# imp-watt-meter.net
KiCad netlist of a schematic drawn in EAGLE
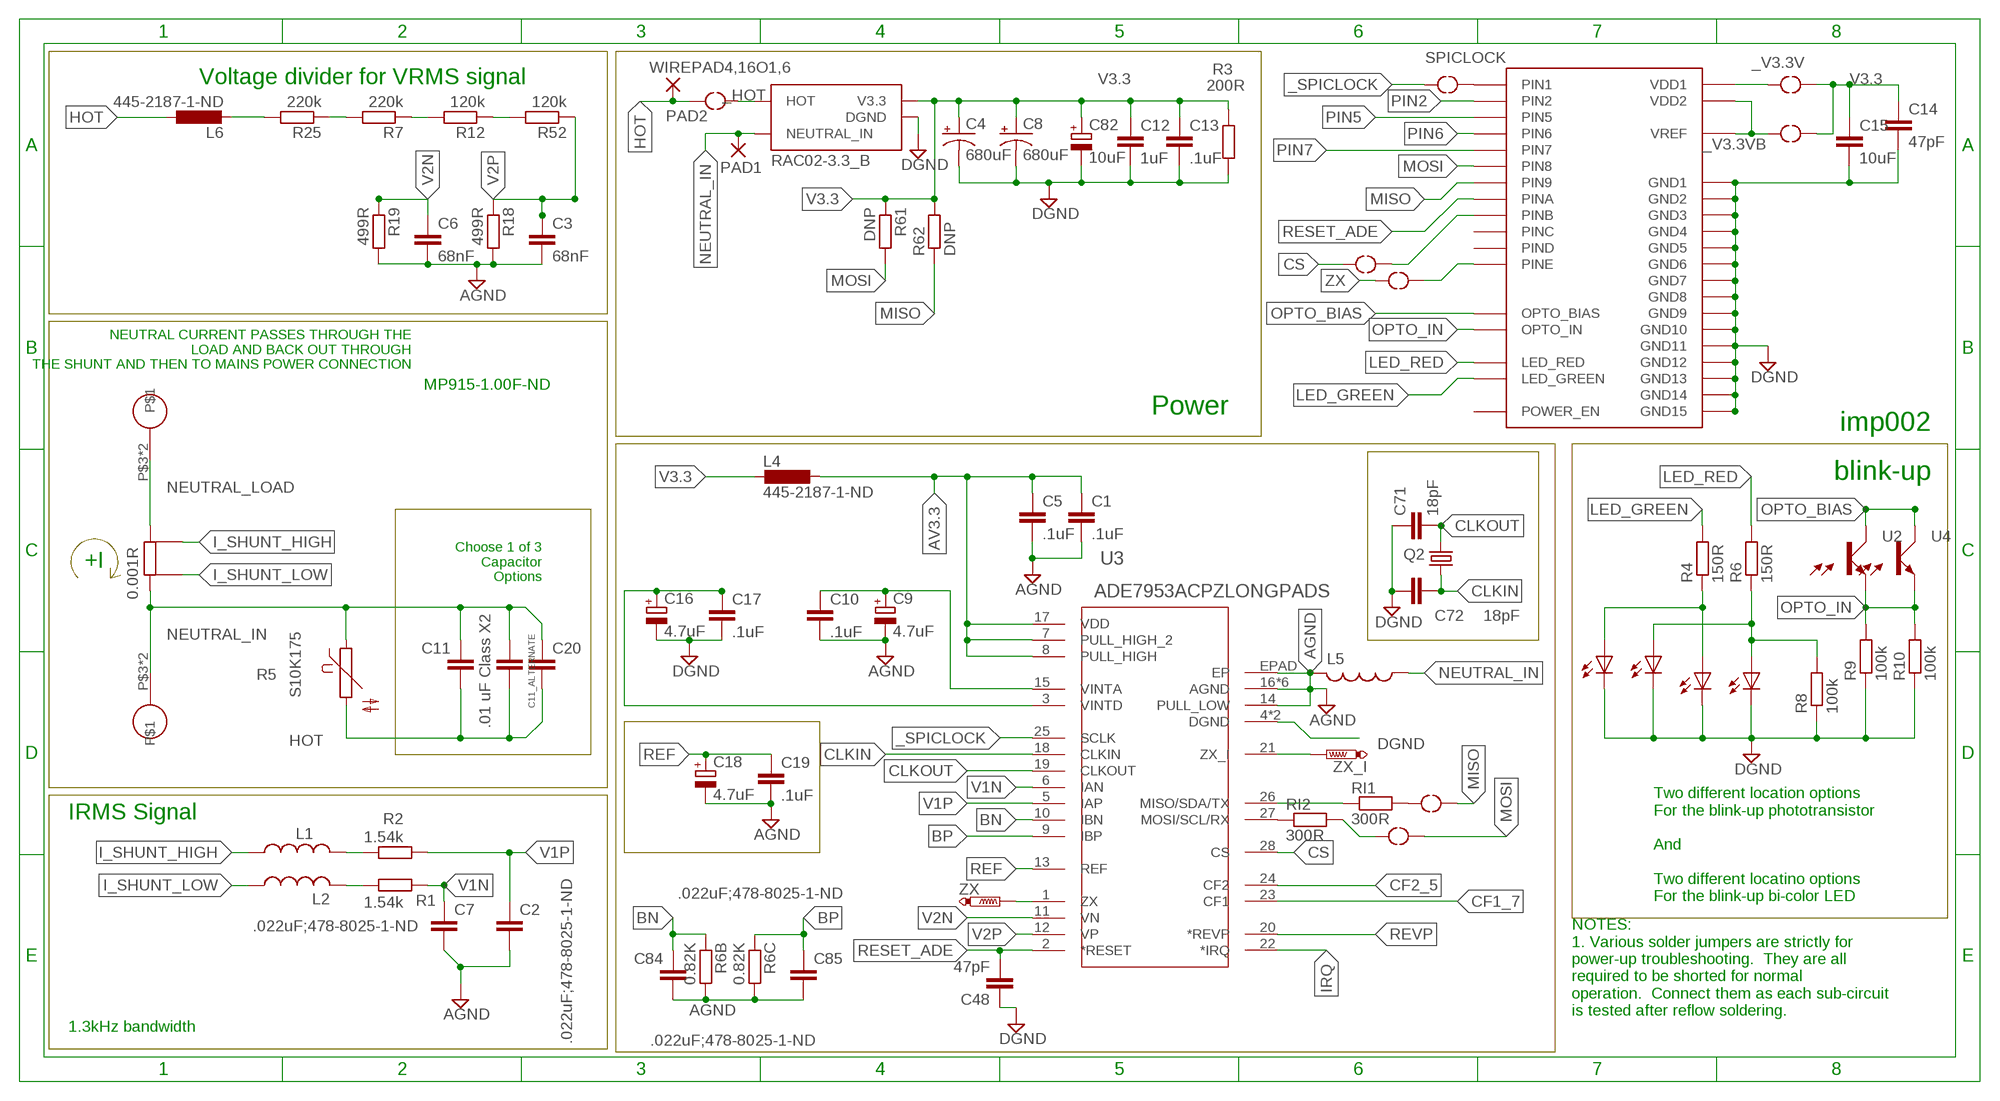
[diagram p0: schematic, sheet 1]

(export (version "E")
  (design (tool "Eeschema 10.0.6"))
  (components
    (comp (ref "0.001R")
      (value "WSLP2726L5000FEA")
      (footprint "eagle-import:WSLP276_VISHAY")
      (libsource (lib "eagle-import") (part "WSLP2726L5000FEA"))
    )
    (comp (ref "C1")
      (value ".1uF")
      (footprint "eagle-import:C0805K@1")
      (libsource (lib "eagle-import") (part "resistor_C-EUC0805K"))
    )
    (comp (ref "C2")
      (value ".022uF;478-8025-1-ND")
      (footprint "eagle-import:C0805K@1")
      (libsource (lib "eagle-import") (part "resistor_C-EUC0805K"))
    )
    (comp (ref "C3")
      (value "68nF")
      (footprint "eagle-import:C0805K@1")
      (libsource (lib "eagle-import") (part "resistor_C-EUC0805K"))
    )
    (comp (ref "C4")
      (value "680uF")
      (footprint "eagle-import:PANASONIC_D")
      (libsource (lib "eagle-import") (part "CAP_POLD"))
    )
    (comp (ref "C5")
      (value ".1uF")
      (footprint "eagle-import:C0805K@1")
      (libsource (lib "eagle-import") (part "resistor_C-EUC0805K"))
    )
    (comp (ref "C6")
      (value "68nF")
      (footprint "eagle-import:C0805K@1")
      (libsource (lib "eagle-import") (part "resistor_C-EUC0805K"))
    )
    (comp (ref "C7")
      (value ".022uF;478-8025-1-ND")
      (footprint "eagle-import:C0805K@1")
      (libsource (lib "eagle-import") (part "resistor_C-EUC0805K"))
    )
    (comp (ref "C8")
      (value "680uF")
      (footprint "eagle-import:PANASONIC_D")
      (libsource (lib "eagle-import") (part "CAP_POLD"))
    )
    (comp (ref "C9")
      (value "4.7uF")
      (footprint "eagle-import:A_3216-18R")
      (libsource (lib "eagle-import") (part "CPOL-EUA/3216-18R"))
    )
    (comp (ref "C10")
      (value ".1uF")
      (footprint "eagle-import:C0805K@1")
      (libsource (lib "eagle-import") (part "resistor_C-EUC0805K"))
    )
    (comp (ref "C11")
      (value ".01 uF Class X2")
      (footprint "eagle-import:C2220K")
      (libsource (lib "eagle-import") (part "C-EUC2220K"))
    )
    (comp (ref "C11_ALTERNATE")
      (value ".01 uF Class X2")
      (footprint "eagle-import:C2220K")
      (libsource (lib "eagle-import") (part "C-EUC2220K"))
    )
    (comp (ref "C12")
      (value "1uF")
      (footprint "eagle-import:C1206K")
      (libsource (lib "eagle-import") (part "resistor_C-EUC1206K"))
    )
    (comp (ref "C13")
      (value ".1uF")
      (footprint "eagle-import:C0805K@1")
      (libsource (lib "eagle-import") (part "resistor_C-EUC0805K"))
    )
    (comp (ref "C14")
      (value "47pF")
      (footprint "eagle-import:C0805K@1")
      (libsource (lib "eagle-import") (part "resistor_C-EUC0805K"))
    )
    (comp (ref "C15")
      (value "10uF")
      (footprint "eagle-import:1206")
      (libsource (lib "eagle-import") (part "CAP1206"))
    )
    (comp (ref "C16")
      (value "4.7uF")
      (footprint "eagle-import:A_3216-18R")
      (libsource (lib "eagle-import") (part "CPOL-EUA/3216-18R"))
    )
    (comp (ref "C17")
      (value ".1uF")
      (footprint "eagle-import:C0805K@1")
      (libsource (lib "eagle-import") (part "resistor_C-EUC0805K"))
    )
    (comp (ref "C18")
      (value "4.7uF")
      (footprint "eagle-import:A_3216-18R")
      (libsource (lib "eagle-import") (part "CPOL-EUA/3216-18R"))
    )
    (comp (ref "C19")
      (value ".1uF")
      (footprint "eagle-import:C0805K@1")
      (libsource (lib "eagle-import") (part "resistor_C-EUC0805K"))
    )
    (comp (ref "C20")
      (value "C10/4")
      (footprint "eagle-import:C10B4")
      (libsource (lib "eagle-import") (part "C10/4"))
    )
    (comp (ref "C48")
      (value "47pF")
      (footprint "eagle-import:C0805K@1")
      (libsource (lib "eagle-import") (part "resistor_C-EUC0805K"))
    )
    (comp (ref "C71")
      (value "18pF")
      (footprint "eagle-import:C0805K@1")
      (libsource (lib "eagle-import") (part "resistor_C-EUC0805K"))
    )
    (comp (ref "C72")
      (value "18pF")
      (footprint "eagle-import:C0805K@1")
      (libsource (lib "eagle-import") (part "resistor_C-EUC0805K"))
    )
    (comp (ref "C82")
      (value "10uF")
      (footprint "eagle-import:A_3216-18R")
      (libsource (lib "eagle-import") (part "CPOL-EUA/3216-18R"))
    )
    (comp (ref "C84")
      (value ".022uF;478-8025-1-ND")
      (footprint "eagle-import:C0805K@1")
      (libsource (lib "eagle-import") (part "resistor_C-EUC0805K"))
    )
    (comp (ref "C85")
      (value ".022uF;478-8025-1-ND")
      (footprint "eagle-import:C0805K@1")
      (libsource (lib "eagle-import") (part "resistor_C-EUC0805K"))
    )
    (comp (ref "L1")
      (value "L-USL4516C")
      (footprint "eagle-import:L4516C")
      (libsource (lib "eagle-import") (part "L-USL4516C"))
    )
    (comp (ref "L2")
      (value "L-USL4516C")
      (footprint "eagle-import:L4516C")
      (libsource (lib "eagle-import") (part "L-USL4516C"))
    )
    (comp (ref "L4")
      (value "445-2187-1-ND")
      (footprint "eagle-import:L2012C")
      (libsource (lib "eagle-import") (part "L-EUL2012C"))
    )
    (comp (ref "L5")
      (value "L-USL4516C")
      (footprint "eagle-import:L4516C")
      (libsource (lib "eagle-import") (part "L-USL4516C"))
    )
    (comp (ref "L6")
      (value "445-2187-1-ND")
      (footprint "eagle-import:L2012C")
      (libsource (lib "eagle-import") (part "L-EUL2012C"))
    )
    (comp (ref "PAD1")
      (value "WIREPAD4,16O1,6")
      (footprint "eagle-import:4,16O1,6")
      (libsource (lib "eagle-import") (part "WIREPAD4,16O1,6"))
    )
    (comp (ref "PAD2")
      (value "WIREPAD4,16O1,6")
      (footprint "eagle-import:4,16O1,6")
      (libsource (lib "eagle-import") (part "WIREPAD4,16O1,6"))
    )
    (comp (ref "Q2")
      (value "535-10200-1-ND")
      (footprint "eagle-import:SM49")
      (libsource (lib "eagle-import") (part "CRYSTALSM49"))
    )
    (comp (ref "R1")
      (value "1.54k")
      (footprint "eagle-import:C0805K")
      (libsource (lib "eagle-import") (part "R-EU_"))
    )
    (comp (ref "R2")
      (value "1.54k")
      (footprint "eagle-import:C0805K")
      (libsource (lib "eagle-import") (part "R-EU_"))
    )
    (comp (ref "R3")
      (value "200R")
      (footprint "eagle-import:M1206")
      (libsource (lib "eagle-import") (part "R-EU_M1206"))
    )
    (comp (ref "R4")
      (value "150R")
      (footprint "eagle-import:R0805")
      (libsource (lib "eagle-import") (part "R-EU_R0805"))
    )
    (comp (ref "R5")
      (value "S10K175")
      (footprint "eagle-import:S10K175")
      (libsource (lib "eagle-import") (part "S10K175"))
    )
    (comp (ref "R6")
      (value "150R")
      (footprint "eagle-import:R0805")
      (libsource (lib "eagle-import") (part "R-EU_R0805"))
    )
    (comp (ref "R6B")
      (value "0.82K")
      (footprint "eagle-import:C0805K")
      (libsource (lib "eagle-import") (part "R-EU_"))
    )
    (comp (ref "R6C")
      (value "0.82K")
      (footprint "eagle-import:C0805K")
      (libsource (lib "eagle-import") (part "R-EU_"))
    )
    (comp (ref "R7")
      (value "220k")
      (footprint "eagle-import:R2010")
      (libsource (lib "eagle-import") (part "R-EU_R2010"))
    )
    (comp (ref "R8")
      (value "100k")
      (footprint "eagle-import:R0805")
      (libsource (lib "eagle-import") (part "R-EU_R0805"))
    )
    (comp (ref "R9")
      (value "100k")
      (footprint "eagle-import:R0805")
      (libsource (lib "eagle-import") (part "R-EU_R0805"))
    )
    (comp (ref "R10")
      (value "100k")
      (footprint "eagle-import:R0805")
      (libsource (lib "eagle-import") (part "R-EU_R0805"))
    )
    (comp (ref "R12")
      (value "120k")
      (footprint "eagle-import:M1206")
      (libsource (lib "eagle-import") (part "R-EU_M1206"))
    )
    (comp (ref "R18")
      (value "499R")
      (footprint "eagle-import:C0805K")
      (libsource (lib "eagle-import") (part "R-EU_"))
    )
    (comp (ref "R19")
      (value "499R")
      (footprint "eagle-import:C0805K")
      (libsource (lib "eagle-import") (part "R-EU_"))
    )
    (comp (ref "R25")
      (value "220k")
      (footprint "eagle-import:R2010")
      (libsource (lib "eagle-import") (part "R-EU_R2010"))
    )
    (comp (ref "R52")
      (value "120k")
      (footprint "eagle-import:M1206")
      (libsource (lib "eagle-import") (part "R-EU_M1206"))
    )
    (comp (ref "R61")
      (value "DNP")
      (footprint "eagle-import:C0805K")
      (libsource (lib "eagle-import") (part "R-EU_"))
    )
    (comp (ref "R62")
      (value "DNP")
      (footprint "eagle-import:C0805K")
      (libsource (lib "eagle-import") (part "R-EU_"))
    )
    (comp (ref "RI1")
      (value "300R")
      (footprint "eagle-import:R0805@1")
      (libsource (lib "eagle-import") (part "R-US_R0805"))
    )
    (comp (ref "RI2")
      (value "300R")
      (footprint "eagle-import:R0805@1")
      (libsource (lib "eagle-import") (part "R-US_R0805"))
    )
    (comp (ref "U$1")
      (value "RAC02-3.3_B")
      (footprint "eagle-import:RAC02_B")
      (libsource (lib "eagle-import") (part "RAC02-3.3_B"))
    )
    (comp (ref "U$2")
      (value "KEYSTONE_FASTON")
      (footprint "eagle-import:KEYSTONE_FASTON_0.25")
      (libsource (lib "eagle-import") (part "KEYSTONE_FASTON"))
    )
    (comp (ref "U$5")
      (value "IMP002MANUFACTURING")
      (footprint "eagle-import:IMP002")
      (libsource (lib "eagle-import") (part "IMP002MANUFACTURING"))
    )
    (comp (ref "U$10")
      (value "JUMPER2B")
      (footprint "eagle-import:SOLDER_JUMPER2B")
      (libsource (lib "eagle-import") (part "JUMPER2B"))
    )
    (comp (ref "U$11")
      (value "JUMPER2B")
      (footprint "eagle-import:SOLDER_JUMPER2B")
      (libsource (lib "eagle-import") (part "JUMPER2B"))
    )
    (comp (ref "U$12")
      (value "JUMPER2B")
      (footprint "eagle-import:SOLDER_JUMPER2B")
      (libsource (lib "eagle-import") (part "JUMPER2B"))
    )
    (comp (ref "U$13")
      (value "JUMPER2B")
      (footprint "eagle-import:SOLDER_JUMPER2B")
      (libsource (lib "eagle-import") (part "JUMPER2B"))
    )
    (comp (ref "U$15")
      (value "JUMPER2B")
      (footprint "eagle-import:SOLDER_JUMPER2B")
      (libsource (lib "eagle-import") (part "JUMPER2B"))
    )
    (comp (ref "U$16")
      (value "JUMPER3")
      (footprint "eagle-import:SOLDER_JUMPER3")
      (libsource (lib "eagle-import") (part "JUMPER3"))
    )
    (comp (ref "U$17")
      (value "KEYSTONE_FASTON")
      (footprint "eagle-import:KEYSTONE_FASTON_0.25")
      (libsource (lib "eagle-import") (part "KEYSTONE_FASTON"))
    )
    (comp (ref "U$18")
      (value "JUMPER3")
      (footprint "eagle-import:SOLDER_JUMPER3")
      (libsource (lib "eagle-import") (part "JUMPER3"))
    )
    (comp (ref "U$19")
      (value "JUMPER2B")
      (footprint "eagle-import:SOLDER_JUMPER2B")
      (libsource (lib "eagle-import") (part "JUMPER2B"))
    )
    (comp (ref "U1")
      (value "LED_DUAL")
      (footprint "eagle-import:LED-BICOLOR")
      (libsource (lib "eagle-import") (part "LED_DUAL"))
    )
    (comp (ref "U2")
      (value "PHOTOTRANSISTOR0603")
      (footprint "eagle-import:0603")
      (libsource (lib "eagle-import") (part "PHOTOTRANSISTOR0603"))
    )
    (comp (ref "U3")
      (value "ADE7953ACPZLONGPADS")
      (footprint "eagle-import:VQFN-28-D")
      (libsource (lib "eagle-import") (part "ADE7953ACPZ5.0"))
    )
    (comp (ref "U4")
      (value "PHOTOTRANSISTOR0603")
      (footprint "eagle-import:0603")
      (libsource (lib "eagle-import") (part "PHOTOTRANSISTOR0603"))
    )
    (comp (ref "U5")
      (value "LED_DUAL")
      (footprint "eagle-import:LED-BICOLOR")
      (libsource (lib "eagle-import") (part "LED_DUAL"))
    )
    (comp (ref "ZX")
      (value "PTR1TP08R")
      (footprint "eagle-import:TP08R")
      (libsource (lib "eagle-import") (part "PTR1TP08R"))
    )
    (comp (ref "ZX_I")
      (value "PTR1TP08R")
      (footprint "eagle-import:TP08R")
      (libsource (lib "eagle-import") (part "PTR1TP08R"))
    )
  )
  (nets
    (net (code "1") (name "/NEUTRAL_LOAD") (class "Default")
      (node (ref "0.001R") (pin "P$1") (pinfunction "1_P$1") (pintype "passive"))
      (node (ref "0.001R") (pin "P$5") (pinfunction "1_P$5") (pintype "passive"))
      (node (ref "0.001R") (pin "P$6") (pinfunction "1_P$6") (pintype "passive"))
      (node (ref "0.001R") (pin "P$7") (pinfunction "1_P$7") (pintype "passive"))
      (node (ref "U$2") (pin "P$3") (pinfunction "P$1_P$3") (pintype "bidirectional"))
      (node (ref "U$2") (pin "P$4") (pinfunction "P$1_P$4") (pintype "bidirectional"))
    )
    (net (code "3") (name "/_HOT") (class "Default")
      (node (ref "U$1") (pin "P$2") (pinfunction "HOT_P$2") (pintype "input"))
      (node (ref "U$1") (pin "P$7") (pinfunction "HOT_P$7") (pintype "input"))
      (node (ref "U$19") (pin "P$2") (pinfunction "P$2_P$2") (pintype "bidirectional"))
    )
    (net (code "4") (name "/_V3.3V") (class "Default")
      (node (ref "U$16") (pin "P$2") (pinfunction "P$2_P$2") (pintype "bidirectional"))
      (node (ref "U$5") (pin "PAD18") (pinfunction "VDD1_PAD18") (pintype "bidirectional"))
    )
    (net (code "5") (name "/_V3.3VB") (class "Default")
      (node (ref "U$18") (pin "P$2") (pinfunction "P$2_P$2") (pintype "bidirectional"))
      (node (ref "U$5") (pin "PAD33") (pinfunction "VDD2_PAD33") (pintype "bidirectional"))
      (node (ref "U$5") (pin "PAD34") (pinfunction "VREF_PAD34") (pintype "bidirectional"))
    )
    (net (code "6") (name "AGND") (class "Default")
      (node (ref "C1") (pin "2") (pinfunction "2_2") (pintype "passive"))
      (node (ref "C10") (pin "2") (pinfunction "2_2") (pintype "passive"))
      (node (ref "C18") (pin "-") (pinfunction "-_-") (pintype "passive"))
      (node (ref "C19") (pin "2") (pinfunction "2_2") (pintype "passive"))
      (node (ref "C2") (pin "2") (pinfunction "2_2") (pintype "passive"))
      (node (ref "C3") (pin "2") (pinfunction "2_2") (pintype "passive"))
      (node (ref "C5") (pin "2") (pinfunction "2_2") (pintype "passive"))
      (node (ref "C6") (pin "2") (pinfunction "2_2") (pintype "passive"))
      (node (ref "C7") (pin "2") (pinfunction "2_2") (pintype "passive"))
      (node (ref "C84") (pin "2") (pinfunction "2_2") (pintype "passive"))
      (node (ref "C85") (pin "2") (pinfunction "2_2") (pintype "passive"))
      (node (ref "C9") (pin "-") (pinfunction "-_-") (pintype "passive"))
      (node (ref "L5") (pin "2") (pinfunction "2_2") (pintype "passive"))
      (node (ref "R18") (pin "2") (pinfunction "2_2") (pintype "passive"))
      (node (ref "R19") (pin "2") (pinfunction "2_2") (pintype "passive"))
      (node (ref "R6B") (pin "2") (pinfunction "2_2") (pintype "passive"))
      (node (ref "R6C") (pin "2") (pinfunction "2_2") (pintype "passive"))
      (node (ref "U3") (pin "14") (pinfunction "PULL_LOW_14") (pintype "passive"))
      (node (ref "U3") (pin "16") (pinfunction "AGND_16") (pintype "passive"))
      (node (ref "U3") (pin "29") (pinfunction "AGND_29") (pintype "passive"))
      (node (ref "U3") (pin "30") (pinfunction "AGND_30") (pintype "passive"))
      (node (ref "U3") (pin "31") (pinfunction "AGND_31") (pintype "passive"))
      (node (ref "U3") (pin "32") (pinfunction "AGND_32") (pintype "passive"))
      (node (ref "U3") (pin "EPAD") (pinfunction "EP_EPAD") (pintype "passive"))
      (node (ref "U3") (pin "_AGND") (pinfunction "AGND__AGND") (pintype "passive"))
    )
    (net (code "7") (name "AV3.3") (class "Default")
      (node (ref "C1") (pin "1") (pinfunction "1_1") (pintype "passive"))
      (node (ref "C5") (pin "1") (pinfunction "1_1") (pintype "passive"))
      (node (ref "L4") (pin "1") (pinfunction "1_1") (pintype "passive"))
      (node (ref "U3") (pin "17") (pinfunction "VDD_17") (pintype "passive"))
      (node (ref "U3") (pin "7") (pinfunction "PULL_HIGH_2_7") (pintype "passive"))
      (node (ref "U3") (pin "8") (pinfunction "PULL_HIGH_8") (pintype "passive"))
    )
    (net (code "8") (name "BN") (class "Default")
      (node (ref "C84") (pin "1") (pinfunction "1_1") (pintype "passive"))
      (node (ref "R6B") (pin "1") (pinfunction "1_1") (pintype "passive"))
      (node (ref "U3") (pin "10") (pinfunction "IBN_10") (pintype "passive"))
    )
    (net (code "9") (name "BP") (class "Default")
      (node (ref "C85") (pin "1") (pinfunction "1_1") (pintype "passive"))
      (node (ref "R6C") (pin "1") (pinfunction "1_1") (pintype "passive"))
      (node (ref "U3") (pin "9") (pinfunction "IBP_9") (pintype "passive"))
    )
    (net (code "10") (name "CF1_7") (class "Default")
      (node (ref "U3") (pin "23") (pinfunction "CF1_23") (pintype "passive"))
    )
    (net (code "11") (name "CF2_5") (class "Default")
      (node (ref "U3") (pin "24") (pinfunction "CF2_24") (pintype "passive"))
    )
    (net (code "12") (name "CLKIN") (class "Default")
      (node (ref "C72") (pin "2") (pinfunction "2_2") (pintype "passive"))
      (node (ref "Q2") (pin "1") (pinfunction "1_1") (pintype "passive"))
      (node (ref "U3") (pin "18") (pinfunction "CLKIN_18") (pintype "passive"))
    )
    (net (code "13") (name "CLKOUT") (class "Default")
      (node (ref "C71") (pin "2") (pinfunction "2_2") (pintype "passive"))
      (node (ref "Q2") (pin "2") (pinfunction "2_2") (pintype "passive"))
      (node (ref "U3") (pin "19") (pinfunction "CLKOUT_19") (pintype "passive"))
    )
    (net (code "14") (name "CS") (class "Default")
      (node (ref "U$10") (pin "P$2") (pinfunction "P$2_P$2") (pintype "bidirectional"))
      (node (ref "U3") (pin "28") (pinfunction "CS_28") (pintype "passive"))
    )
    (net (code "15") (name "DGND") (class "Default")
      (node (ref "C12") (pin "2") (pinfunction "2_2") (pintype "passive"))
      (node (ref "C13") (pin "2") (pinfunction "2_2") (pintype "passive"))
      (node (ref "C14") (pin "2") (pinfunction "2_2") (pintype "passive"))
      (node (ref "C15") (pin "2") (pinfunction "2_2") (pintype "passive"))
      (node (ref "C16") (pin "-") (pinfunction "-_-") (pintype "passive"))
      (node (ref "C17") (pin "2") (pinfunction "2_2") (pintype "passive"))
      (node (ref "C4") (pin "-") (pinfunction "-_-") (pintype "passive"))
      (node (ref "C48") (pin "1") (pinfunction "1_1") (pintype "passive"))
      (node (ref "C71") (pin "1") (pinfunction "1_1") (pintype "passive"))
      (node (ref "C72") (pin "1") (pinfunction "1_1") (pintype "passive"))
      (node (ref "C8") (pin "-") (pinfunction "-_-") (pintype "passive"))
      (node (ref "C82") (pin "-") (pinfunction "-_-") (pintype "passive"))
      (node (ref "R10") (pin "1") (pinfunction "1_1") (pintype "passive"))
      (node (ref "R3") (pin "2") (pinfunction "2_2") (pintype "passive"))
      (node (ref "R8") (pin "1") (pinfunction "1_1") (pintype "passive"))
      (node (ref "R9") (pin "1") (pinfunction "1_1") (pintype "passive"))
      (node (ref "U$1") (pin "P$10") (pinfunction "DGND_P$10") (pintype "output"))
      (node (ref "U$1") (pin "P$3") (pinfunction "DGND_P$3") (pintype "output"))
      (node (ref "U$1") (pin "P$5") (pinfunction "DGND_P$5") (pintype "output"))
      (node (ref "U$1") (pin "P$8") (pinfunction "DGND_P$8") (pintype "output"))
      (node (ref "U$5") (pin "PAD1") (pinfunction "GND1_PAD1") (pintype "bidirectional"))
      (node (ref "U$5") (pin "PAD13") (pinfunction "GND3_PAD13") (pintype "bidirectional"))
      (node (ref "U$5") (pin "PAD17") (pinfunction "GND4_PAD17") (pintype "bidirectional"))
      (node (ref "U$5") (pin "PAD23") (pinfunction "GND5_PAD23") (pintype "bidirectional"))
      (node (ref "U$5") (pin "PAD24") (pinfunction "GND6_PAD24") (pintype "bidirectional"))
      (node (ref "U$5") (pin "PAD25") (pinfunction "GND7_PAD25") (pintype "bidirectional"))
      (node (ref "U$5") (pin "PAD26") (pinfunction "GND8_PAD26") (pintype "bidirectional"))
      (node (ref "U$5") (pin "PAD27") (pinfunction "GND9_PAD27") (pintype "bidirectional"))
      (node (ref "U$5") (pin "PAD28") (pinfunction "GND10_PAD28") (pintype "bidirectional"))
      (node (ref "U$5") (pin "PAD29") (pinfunction "GND11_PAD29") (pintype "bidirectional"))
      (node (ref "U$5") (pin "PAD30") (pinfunction "GND12_PAD30") (pintype "bidirectional"))
      (node (ref "U$5") (pin "PAD31") (pinfunction "GND13_PAD31") (pintype "bidirectional"))
      (node (ref "U$5") (pin "PAD32") (pinfunction "GND14_PAD32") (pintype "bidirectional"))
      (node (ref "U$5") (pin "PAD35") (pinfunction "GND15_PAD35") (pintype "bidirectional"))
      (node (ref "U$5") (pin "PAD7") (pinfunction "GND2_PAD7") (pintype "bidirectional"))
      (node (ref "U1") (pin "3") (pinfunction "C_3") (pintype "passive"))
      (node (ref "U1") (pin "4") (pinfunction "C_4") (pintype "passive"))
      (node (ref "U3") (pin "4") (pinfunction "DGND_4") (pintype "passive"))
      (node (ref "U3") (pin "_DGND") (pinfunction "DGND__DGND") (pintype "passive"))
      (node (ref "U5") (pin "3") (pinfunction "C_3") (pintype "passive"))
      (node (ref "U5") (pin "4") (pinfunction "C_4") (pintype "passive"))
    )
    (net (code "16") (name "HOT") (class "Default")
      (node (ref "C11") (pin "1") (pinfunction "1_1") (pintype "passive"))
      (node (ref "C11_ALTERNATE") (pin "1") (pinfunction "1_1") (pintype "passive"))
      (node (ref "C20") (pin "2") (pinfunction "2_2") (pintype "passive"))
      (node (ref "L6") (pin "1") (pinfunction "1_1") (pintype "passive"))
      (node (ref "PAD2") (pin "1") (pinfunction "P_1") (pintype "passive"))
      (node (ref "R5") (pin "2") (pinfunction "2_2") (pintype "passive"))
      (node (ref "U$19") (pin "P$1") (pinfunction "P$1_P$1") (pintype "bidirectional"))
    )
    (net (code "17") (name "IRQ") (class "Default")
      (node (ref "U3") (pin "22") (pinfunction "*IRQ_22") (pintype "passive"))
    )
    (net (code "18") (name "I_SHUNT_HIGH") (class "Default")
      (node (ref "0.001R") (pin "P$3") (pinfunction "P$1_P$3") (pintype "bidirectional"))
      (node (ref "L1") (pin "1") (pinfunction "1_1") (pintype "passive"))
    )
    (net (code "19") (name "I_SHUNT_LOW") (class "Default")
      (node (ref "0.001R") (pin "P$4") (pinfunction "P$2_P$4") (pintype "bidirectional"))
      (node (ref "L2") (pin "1") (pinfunction "1_1") (pintype "passive"))
    )
    (net (code "20") (name "LED_GREEN") (class "Default")
      (node (ref "R4") (pin "2") (pinfunction "2_2") (pintype "passive"))
      (node (ref "U$5") (pin "PAD3") (pinfunction "LED_GREEN_PAD3") (pintype "bidirectional"))
    )
    (net (code "21") (name "LED_RED") (class "Default")
      (node (ref "R6") (pin "2") (pinfunction "2_2") (pintype "passive"))
      (node (ref "U$5") (pin "PAD4") (pinfunction "LED_RED_PAD4") (pintype "bidirectional"))
    )
    (net (code "22") (name "MISO") (class "Default")
      (node (ref "R62") (pin "1") (pinfunction "1_1") (pintype "passive"))
      (node (ref "U$13") (pin "P$1") (pinfunction "P$1_P$1") (pintype "bidirectional"))
      (node (ref "U$5") (pin "PAD14") (pinfunction "PIN9_PAD14") (pintype "bidirectional"))
    )
    (net (code "23") (name "MOSI") (class "Default")
      (node (ref "R61") (pin "2") (pinfunction "2_2") (pintype "passive"))
      (node (ref "U$12") (pin "P$1") (pinfunction "P$1_P$1") (pintype "bidirectional"))
      (node (ref "U$5") (pin "PAD22") (pinfunction "PIN8_PAD22") (pintype "bidirectional"))
    )
    (net (code "24") (name "NEUTRAL_IN") (class "Default")
      (node (ref "0.001R") (pin "P$10") (pinfunction "2_P$10") (pintype "passive"))
      (node (ref "0.001R") (pin "P$2") (pinfunction "2_P$2") (pintype "passive"))
      (node (ref "0.001R") (pin "P$8") (pinfunction "2_P$8") (pintype "passive"))
      (node (ref "0.001R") (pin "P$9") (pinfunction "2_P$9") (pintype "passive"))
      (node (ref "C11") (pin "2") (pinfunction "2_2") (pintype "passive"))
      (node (ref "C11_ALTERNATE") (pin "2") (pinfunction "2_2") (pintype "passive"))
      (node (ref "C20") (pin "1") (pinfunction "1_1") (pintype "passive"))
      (node (ref "L5") (pin "1") (pinfunction "1_1") (pintype "passive"))
      (node (ref "PAD1") (pin "1") (pinfunction "P_1") (pintype "passive"))
      (node (ref "R5") (pin "1") (pinfunction "1_1") (pintype "passive"))
      (node (ref "U$1") (pin "P$1") (pinfunction "NEUTRAL_IN_P$1") (pintype "passive"))
      (node (ref "U$1") (pin "P$6") (pinfunction "NEUTRAL_IN_P$6") (pintype "passive"))
      (node (ref "U$17") (pin "P$3") (pinfunction "P$1_P$3") (pintype "bidirectional"))
      (node (ref "U$17") (pin "P$4") (pinfunction "P$1_P$4") (pintype "bidirectional"))
    )
    (net (code "25") (name "Net-(L1-Pad2)") (class "Default")
      (node (ref "L1") (pin "2") (pinfunction "2_2") (pintype "passive"))
      (node (ref "R2") (pin "2") (pinfunction "2_2") (pintype "passive"))
    )
    (net (code "26") (name "Net-(L2-Pad2)") (class "Default")
      (node (ref "L2") (pin "2") (pinfunction "2_2") (pintype "passive"))
      (node (ref "R1") (pin "2") (pinfunction "2_2") (pintype "passive"))
    )
    (net (code "27") (name "Net-(L6-Pad2)") (class "Default")
      (node (ref "L6") (pin "2") (pinfunction "2_2") (pintype "passive"))
      (node (ref "R25") (pin "2") (pinfunction "2_2") (pintype "passive"))
    )
    (net (code "28") (name "Net-(R12-Pad1)") (class "Default")
      (node (ref "R12") (pin "1") (pinfunction "1_1") (pintype "passive"))
      (node (ref "R52") (pin "2") (pinfunction "2_2") (pintype "passive"))
    )
    (net (code "29") (name "Net-(R12-Pad2)") (class "Default")
      (node (ref "R12") (pin "2") (pinfunction "2_2") (pintype "passive"))
      (node (ref "R7") (pin "1") (pinfunction "1_1") (pintype "passive"))
    )
    (net (code "30") (name "Net-(R25-Pad1)") (class "Default")
      (node (ref "R25") (pin "1") (pinfunction "1_1") (pintype "passive"))
      (node (ref "R7") (pin "2") (pinfunction "2_2") (pintype "passive"))
    )
    (net (code "31") (name "Net-(RI1-Pad2)") (class "Default")
      (node (ref "RI1") (pin "2") (pinfunction "2_2") (pintype "passive"))
      (node (ref "U$13") (pin "P$2") (pinfunction "P$2_P$2") (pintype "bidirectional"))
    )
    (net (code "32") (name "Net-(RI2-Pad2)") (class "Default")
      (node (ref "RI2") (pin "2") (pinfunction "2_2") (pintype "passive"))
      (node (ref "U$12") (pin "P$2") (pinfunction "P$2_P$2") (pintype "bidirectional"))
    )
    (net (code "33") (name "Net-(U$5-PIN1)") (class "Default")
      (node (ref "U$11") (pin "P$1") (pinfunction "P$1_P$1") (pintype "bidirectional"))
      (node (ref "U$5") (pin "PAD15") (pinfunction "PIN1_PAD15") (pintype "bidirectional"))
    )
    (net (code "34") (name "Net-(U$5-PINB)") (class "Default")
      (node (ref "U$10") (pin "P$1") (pinfunction "P$1_P$1") (pintype "bidirectional"))
      (node (ref "U$5") (pin "PAD9") (pinfunction "PINB_PAD9") (pintype "bidirectional"))
    )
    (net (code "35") (name "Net-(U$5-PINE)") (class "Default")
      (node (ref "U$15") (pin "P$1") (pinfunction "P$1_P$1") (pintype "bidirectional"))
      (node (ref "U$5") (pin "PAD12") (pinfunction "PINE_PAD12") (pintype "bidirectional"))
    )
    (net (code "36") (name "Net-(U1A-A)") (class "Default")
      (node (ref "R4") (pin "1") (pinfunction "1_1") (pintype "passive"))
      (node (ref "U1") (pin "1") (pinfunction "A_1") (pintype "passive"))
      (node (ref "U5") (pin "1") (pinfunction "A_1") (pintype "passive"))
    )
    (net (code "37") (name "Net-(U1B-A)") (class "Default")
      (node (ref "R6") (pin "1") (pinfunction "1_1") (pintype "passive"))
      (node (ref "R8") (pin "2") (pinfunction "2_2") (pintype "passive"))
      (node (ref "U1") (pin "2") (pinfunction "A_2") (pintype "passive"))
      (node (ref "U5") (pin "2") (pinfunction "A_2") (pintype "passive"))
    )
    (net (code "38") (name "Net-(U3-MISO{slash}SDA{slash}TX)") (class "Default")
      (node (ref "RI1") (pin "1") (pinfunction "1_1") (pintype "passive"))
      (node (ref "U3") (pin "26") (pinfunction "MISO/SDA/TX_26") (pintype "passive"))
    )
    (net (code "39") (name "Net-(U3-MOSI{slash}SCL{slash}RX)") (class "Default")
      (node (ref "RI2") (pin "1") (pinfunction "1_1") (pintype "passive"))
      (node (ref "U3") (pin "27") (pinfunction "MOSI/SCL/RX_27") (pintype "passive"))
    )
    (net (code "40") (name "Net-(U3-VINTA)") (class "Default")
      (node (ref "C10") (pin "1") (pinfunction "1_1") (pintype "passive"))
      (node (ref "C9") (pin "+") (pinfunction "+_+") (pintype "passive"))
      (node (ref "U3") (pin "15") (pinfunction "VINTA_15") (pintype "passive"))
    )
    (net (code "41") (name "Net-(U3-VINTD)") (class "Default")
      (node (ref "C16") (pin "+") (pinfunction "+_+") (pintype "passive"))
      (node (ref "C17") (pin "1") (pinfunction "1_1") (pintype "passive"))
      (node (ref "U3") (pin "3") (pinfunction "VINTD_3") (pintype "passive"))
    )
    (net (code "42") (name "Net-(U3-ZX_I)") (class "Default")
      (node (ref "U3") (pin "21") (pinfunction "ZX_I_21") (pintype "passive"))
      (node (ref "ZX_I") (pin "TP") (pinfunction "TP_TP") (pintype "input"))
    )
    (net (code "43") (name "OPTO_BIAS") (class "Default")
      (node (ref "U$5") (pin "PAD2") (pinfunction "OPTO_BIAS_PAD2") (pintype "bidirectional"))
      (node (ref "U2") (pin "1") (pinfunction "C_1") (pintype "passive"))
      (node (ref "U4") (pin "1") (pinfunction "C_1") (pintype "passive"))
    )
    (net (code "44") (name "OPTO_IN") (class "Default")
      (node (ref "R10") (pin "2") (pinfunction "2_2") (pintype "passive"))
      (node (ref "R9") (pin "2") (pinfunction "2_2") (pintype "passive"))
      (node (ref "U$5") (pin "PAD6") (pinfunction "OPTO_IN_PAD6") (pintype "bidirectional"))
      (node (ref "U2") (pin "2") (pinfunction "E_2") (pintype "passive"))
      (node (ref "U4") (pin "2") (pinfunction "E_2") (pintype "passive"))
    )
    (net (code "45") (name "PIN2") (class "Default")
      (node (ref "U$5") (pin "PAD16") (pinfunction "PIN2_PAD16") (pintype "bidirectional"))
    )
    (net (code "46") (name "PIN5") (class "Default")
      (node (ref "U$5") (pin "PAD19") (pinfunction "PIN5_PAD19") (pintype "bidirectional"))
    )
    (net (code "47") (name "PIN6") (class "Default")
      (node (ref "U$5") (pin "PAD20") (pinfunction "PIN6_PAD20") (pintype "bidirectional"))
    )
    (net (code "48") (name "PIN7") (class "Default")
      (node (ref "U$5") (pin "PAD21") (pinfunction "PIN7_PAD21") (pintype "bidirectional"))
    )
    (net (code "49") (name "REF") (class "Default")
      (node (ref "C18") (pin "+") (pinfunction "+_+") (pintype "passive"))
      (node (ref "C19") (pin "1") (pinfunction "1_1") (pintype "passive"))
      (node (ref "U3") (pin "13") (pinfunction "REF_13") (pintype "passive"))
    )
    (net (code "50") (name "RESET_ADE") (class "Default")
      (node (ref "C48") (pin "2") (pinfunction "2_2") (pintype "passive"))
      (node (ref "U$5") (pin "PAD8") (pinfunction "PINA_PAD8") (pintype "bidirectional"))
      (node (ref "U3") (pin "2") (pinfunction "*RESET_2") (pintype "passive"))
    )
    (net (code "51") (name "REVP") (class "Default")
      (node (ref "U3") (pin "20") (pinfunction "*REVP_20") (pintype "passive"))
    )
    (net (code "52") (name "V1N") (class "Default")
      (node (ref "C7") (pin "1") (pinfunction "1_1") (pintype "passive"))
      (node (ref "R1") (pin "1") (pinfunction "1_1") (pintype "passive"))
      (node (ref "U3") (pin "6") (pinfunction "IAN_6") (pintype "passive"))
    )
    (net (code "53") (name "V1P") (class "Default")
      (node (ref "C2") (pin "1") (pinfunction "1_1") (pintype "passive"))
      (node (ref "R2") (pin "1") (pinfunction "1_1") (pintype "passive"))
      (node (ref "U3") (pin "5") (pinfunction "IAP_5") (pintype "passive"))
    )
    (net (code "54") (name "V2N") (class "Default")
      (node (ref "C6") (pin "1") (pinfunction "1_1") (pintype "passive"))
      (node (ref "R19") (pin "1") (pinfunction "1_1") (pintype "passive"))
      (node (ref "U3") (pin "11") (pinfunction "VN_11") (pintype "passive"))
    )
    (net (code "55") (name "V2P") (class "Default")
      (node (ref "C3") (pin "1") (pinfunction "1_1") (pintype "passive"))
      (node (ref "R18") (pin "1") (pinfunction "1_1") (pintype "passive"))
      (node (ref "R52") (pin "1") (pinfunction "1_1") (pintype "passive"))
      (node (ref "U3") (pin "12") (pinfunction "VP_12") (pintype "passive"))
    )
    (net (code "56") (name "V3.3") (class "Default")
      (node (ref "C12") (pin "1") (pinfunction "1_1") (pintype "passive"))
      (node (ref "C13") (pin "1") (pinfunction "1_1") (pintype "passive"))
      (node (ref "C14") (pin "1") (pinfunction "1_1") (pintype "passive"))
      (node (ref "C15") (pin "1") (pinfunction "1_1") (pintype "passive"))
      (node (ref "C4") (pin "+") (pinfunction "+_+") (pintype "passive"))
      (node (ref "C8") (pin "+") (pinfunction "+_+") (pintype "passive"))
      (node (ref "C82") (pin "+") (pinfunction "+_+") (pintype "passive"))
      (node (ref "L4") (pin "2") (pinfunction "2_2") (pintype "passive"))
      (node (ref "R3") (pin "1") (pinfunction "1_1") (pintype "passive"))
      (node (ref "R61") (pin "1") (pinfunction "1_1") (pintype "passive"))
      (node (ref "R62") (pin "2") (pinfunction "2_2") (pintype "passive"))
      (node (ref "U$1") (pin "P$4") (pinfunction "V3.3_P$4") (pintype "output"))
      (node (ref "U$1") (pin "P$9") (pinfunction "V3.3_P$9") (pintype "output"))
      (node (ref "U$16") (pin "P$1") (pinfunction "P$1_P$1") (pintype "bidirectional"))
      (node (ref "U$18") (pin "P$1") (pinfunction "P$1_P$1") (pintype "bidirectional"))
    )
    (net (code "57") (name "ZX") (class "Default")
      (node (ref "U$15") (pin "P$2") (pinfunction "P$2_P$2") (pintype "bidirectional"))
      (node (ref "U3") (pin "1") (pinfunction "ZX_1") (pintype "passive"))
      (node (ref "ZX") (pin "TP") (pinfunction "TP_TP") (pintype "input"))
    )
    (net (code "58") (name "_SPICLOCK") (class "Default")
      (node (ref "U$11") (pin "P$2") (pinfunction "P$2_P$2") (pintype "bidirectional"))
      (node (ref "U3") (pin "25") (pinfunction "SCLK_25") (pintype "passive"))
    )
    (net (code "59") (name "unconnected-(U$5-PINC-PadPAD10)") (class "Default")
      (node (ref "U$5") (pin "PAD10") (pinfunction "PINC_PAD10") (pintype "bidirectional"))
    )
    (net (code "60") (name "unconnected-(U$5-PIND-PadPAD11)") (class "Default")
      (node (ref "U$5") (pin "PAD11") (pinfunction "PIND_PAD11") (pintype "bidirectional"))
    )
    (net (code "61") (name "unconnected-(U$5-POWER_EN-PadPAD5)") (class "Default")
      (node (ref "U$5") (pin "PAD5") (pinfunction "POWER_EN_PAD5") (pintype "bidirectional"))
    )
  )
)
